# TSOC_NEOLED.net
KiCad netlist of a schematic drawn in EAGLE
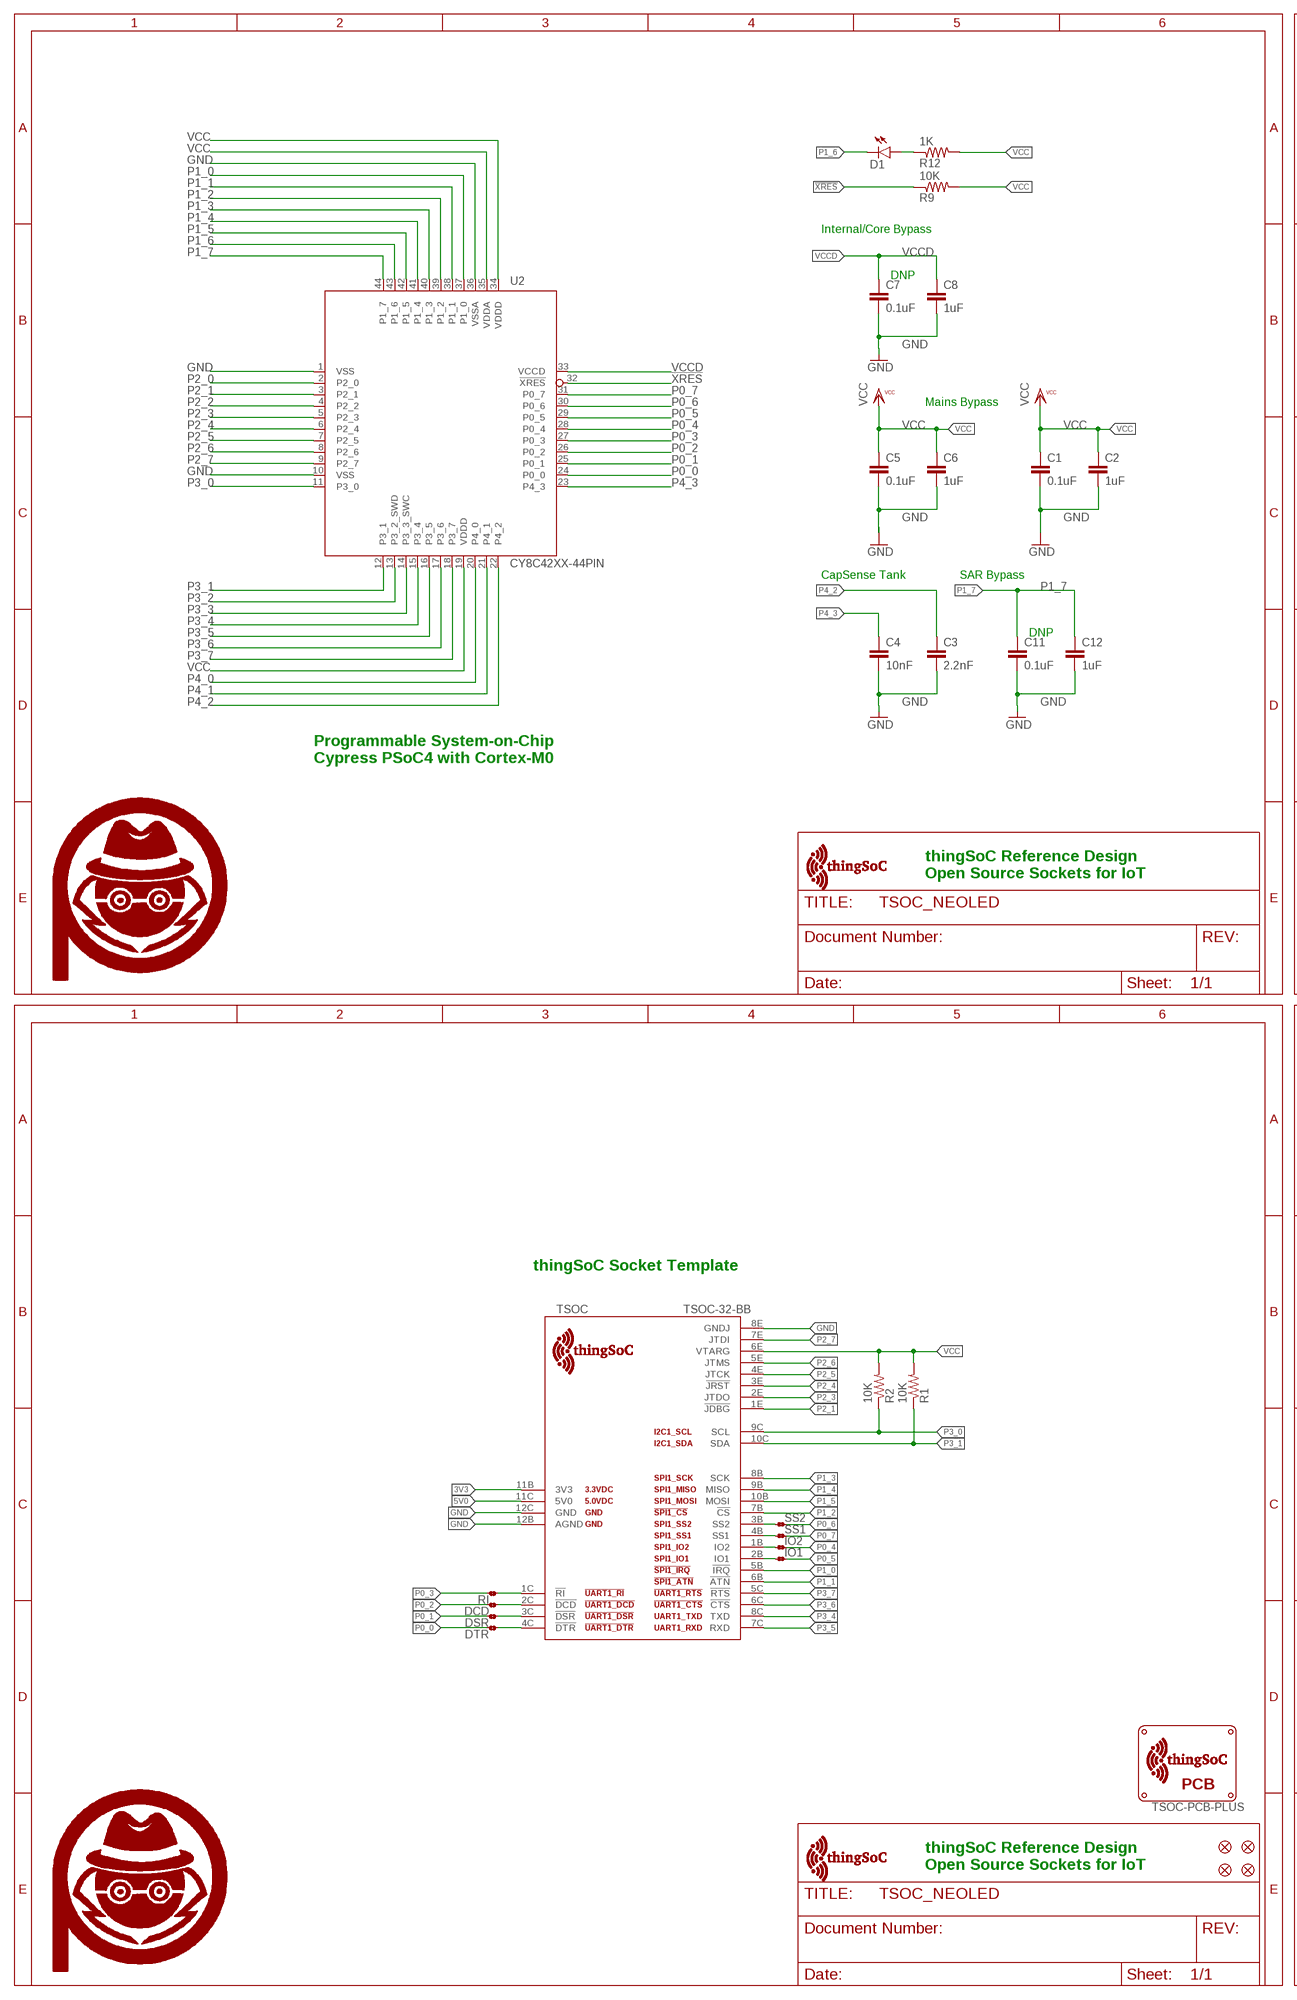
[diagram p0: schematic, sheet 1, part 1 of 2]
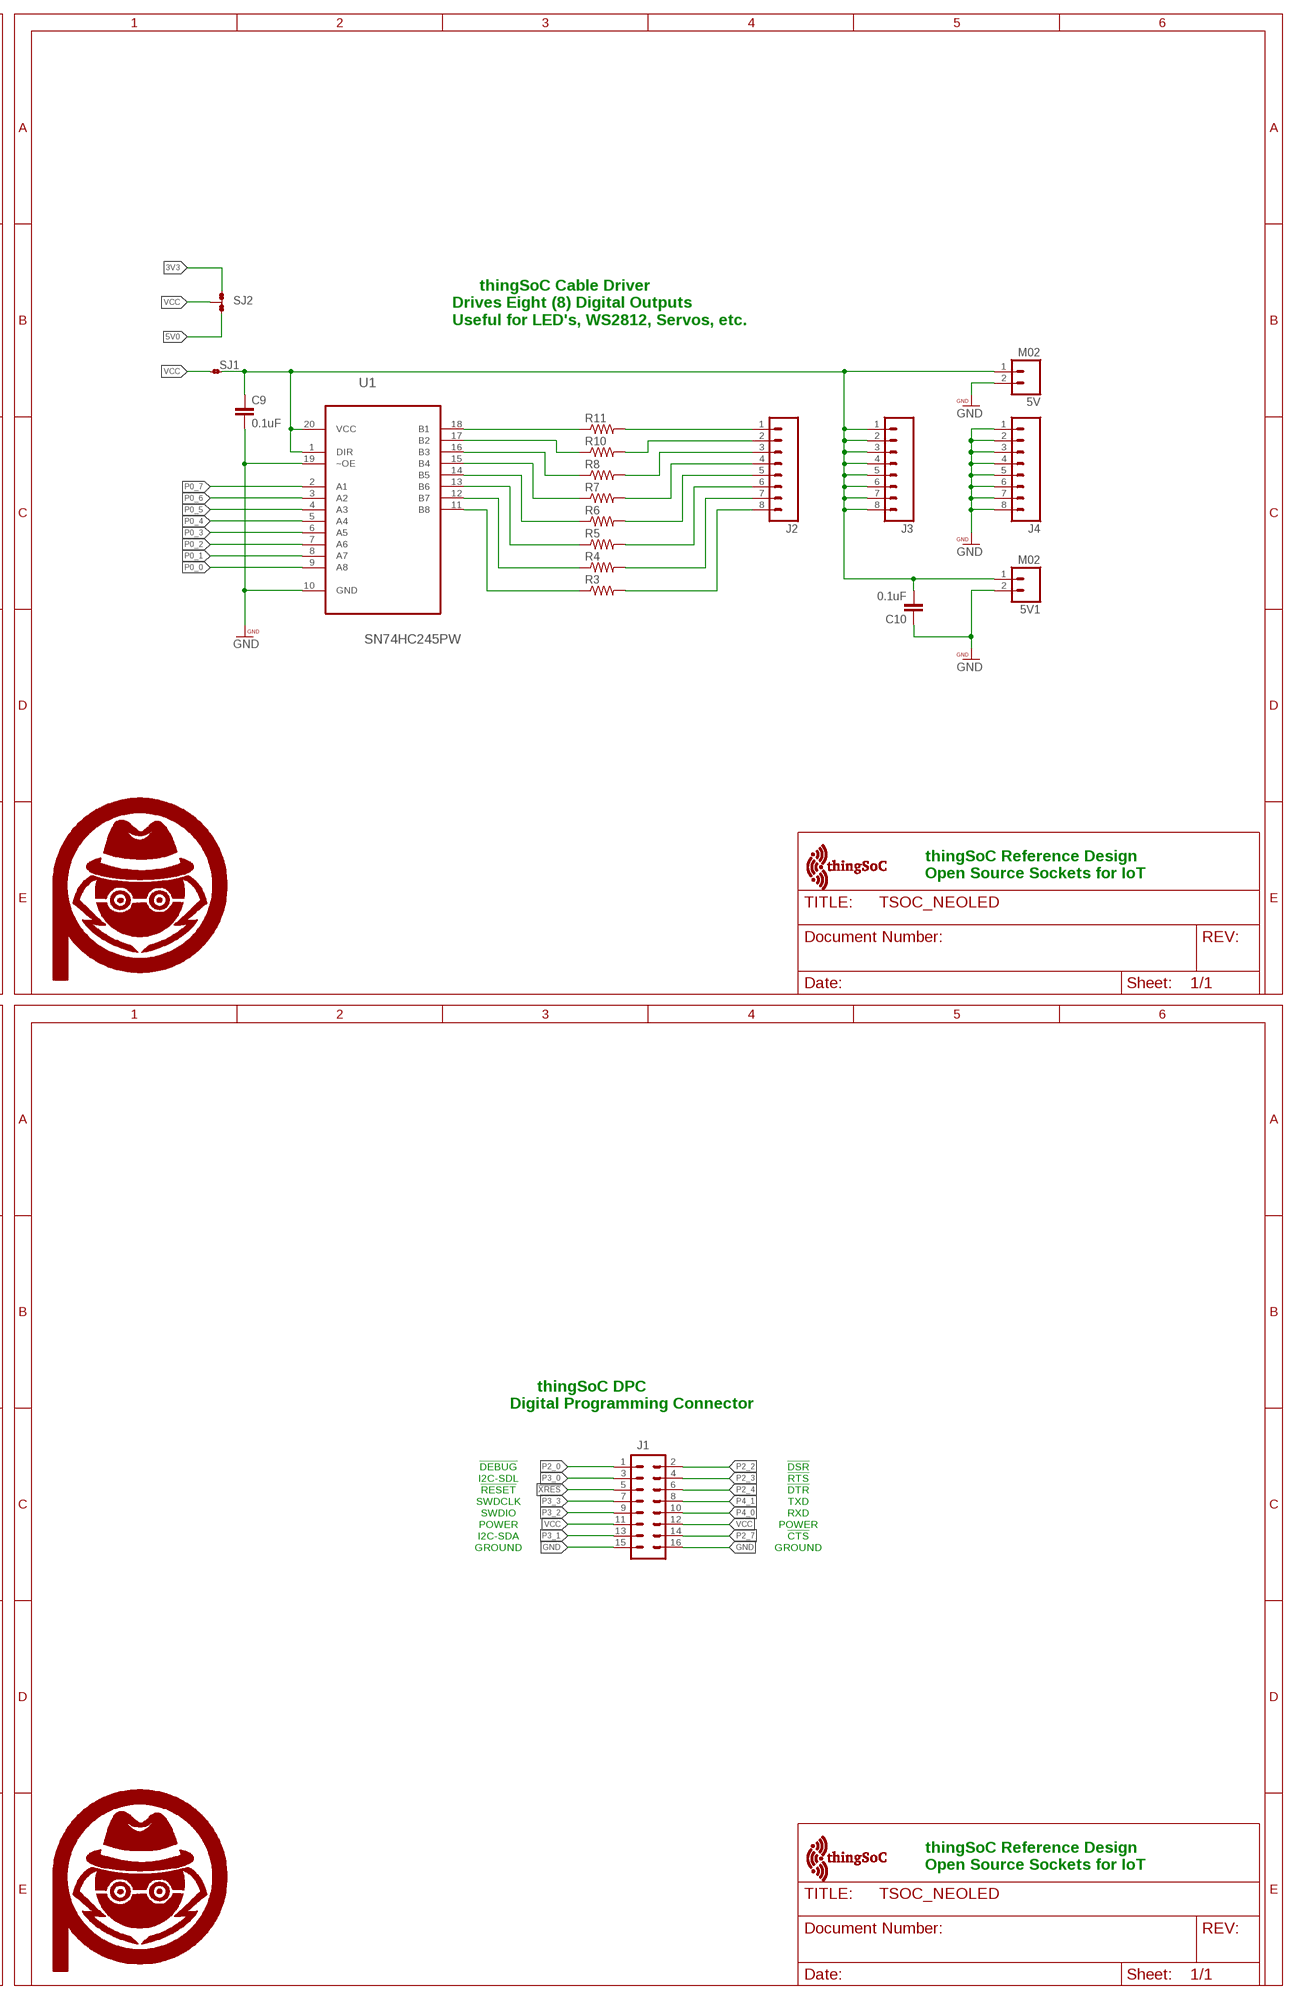
[diagram p1: schematic, sheet 1, part 2 of 2]

(export (version "E")
  (design (tool "Eeschema 10.0.6"))
  (components
    (comp (ref "$$U$1")
      (value "TSOC-LOGO-SMALL")
      (footprint "eagle-import:TSOC-LOGO-SML")
      (libsource (lib "eagle-import") (part "TSOC-LOGO-SMALL"))
    )
    (comp (ref "$$U$2")
      (value "TSOC-LOGO-MED")
      (footprint "eagle-import:TSOC-LOGO-MED")
      (libsource (lib "eagle-import") (part "TSOC-LOGO-MED"))
    )
    (comp (ref "5V")
      (value "M02")
      (footprint "eagle-import:1X02")
      (libsource (lib "eagle-import") (part "M02"))
    )
    (comp (ref "5V1")
      (value "M02")
      (footprint "eagle-import:1X02")
      (libsource (lib "eagle-import") (part "M02"))
    )
    (comp (ref "C1")
      (value "0.1uF")
      (footprint "eagle-import:0603-CAP")
      (libsource (lib "eagle-import") (part "CAP0603-CAP"))
    )
    (comp (ref "C2")
      (value "1uF")
      (footprint "eagle-import:0603-CAP")
      (libsource (lib "eagle-import") (part "CAP0603-CAP"))
    )
    (comp (ref "C3")
      (value "2.2nF")
      (footprint "eagle-import:0603-CAP")
      (libsource (lib "eagle-import") (part "CAP0603-CAP"))
    )
    (comp (ref "C4")
      (value "10nF")
      (footprint "eagle-import:0603-CAP")
      (libsource (lib "eagle-import") (part "CAP0603-CAP"))
    )
    (comp (ref "C5")
      (value "0.1uF")
      (footprint "eagle-import:0603-CAP")
      (libsource (lib "eagle-import") (part "CAP0603-CAP"))
    )
    (comp (ref "C6")
      (value "1uF")
      (footprint "eagle-import:0603-CAP")
      (libsource (lib "eagle-import") (part "CAP0603-CAP"))
    )
    (comp (ref "C7")
      (value "0.1uF")
      (footprint "eagle-import:0603-CAP")
      (libsource (lib "eagle-import") (part "CAP0603-CAP"))
    )
    (comp (ref "C8")
      (value "1uF")
      (footprint "eagle-import:0603-CAP")
      (libsource (lib "eagle-import") (part "CAP0603-CAP"))
    )
    (comp (ref "C9")
      (value "0.1uF")
      (footprint "eagle-import:0603-CAP")
      (libsource (lib "eagle-import") (part "CAP0603-CAP"))
    )
    (comp (ref "C10")
      (value "0.1uF")
      (footprint "eagle-import:0603-CAP")
      (libsource (lib "eagle-import") (part "CAP0603-CAP"))
    )
    (comp (ref "C11")
      (value "0.1uF")
      (footprint "eagle-import:0603-CAP")
      (libsource (lib "eagle-import") (part "CAP0603-CAP"))
    )
    (comp (ref "C12")
      (value "1uF")
      (footprint "eagle-import:0603-CAP")
      (libsource (lib "eagle-import") (part "CAP0603-CAP"))
    )
    (comp (ref "D1")
      (value "LED0603")
      (footprint "eagle-import:LED-0603")
      (libsource (lib "eagle-import") (part "LED0603"))
    )
    (comp (ref "DCD")
      (value "JMP-2-NO")
      (footprint "eagle-import:JMP-2-NO")
      (libsource (lib "eagle-import") (part "JMP-2-NO"))
    )
    (comp (ref "DSR")
      (value "JMP-2-NO")
      (footprint "eagle-import:JMP-2-NO")
      (libsource (lib "eagle-import") (part "JMP-2-NO"))
    )
    (comp (ref "DTR")
      (value "JMP-2-NO")
      (footprint "eagle-import:JMP-2-NO")
      (libsource (lib "eagle-import") (part "JMP-2-NO"))
    )
    (comp (ref "FID1")
      (value "FIDUCIALUFIDUCIAL")
      (footprint "eagle-import:MICRO-FIDUCIAL")
      (libsource (lib "eagle-import") (part "FIDUCIALUFIDUCIAL"))
    )
    (comp (ref "FID2")
      (value "FIDUCIALUFIDUCIAL")
      (footprint "eagle-import:MICRO-FIDUCIAL")
      (libsource (lib "eagle-import") (part "FIDUCIALUFIDUCIAL"))
    )
    (comp (ref "FID3")
      (value "FIDUCIALUFIDUCIAL")
      (footprint "eagle-import:MICRO-FIDUCIAL")
      (libsource (lib "eagle-import") (part "FIDUCIALUFIDUCIAL"))
    )
    (comp (ref "FID4")
      (value "FIDUCIALUFIDUCIAL")
      (footprint "eagle-import:MICRO-FIDUCIAL")
      (libsource (lib "eagle-import") (part "FIDUCIALUFIDUCIAL"))
    )
    (comp (ref "IO1")
      (value "JMP-2-NO")
      (footprint "eagle-import:JMP-2-NO")
      (libsource (lib "eagle-import") (part "JMP-2-NO"))
    )
    (comp (ref "IO2")
      (value "JMP-2-NO")
      (footprint "eagle-import:JMP-2-NO")
      (libsource (lib "eagle-import") (part "JMP-2-NO"))
    )
    (comp (ref "J1")
      (value "M08X2")
      (footprint "eagle-import:2X8")
      (libsource (lib "eagle-import") (part "M08X2"))
    )
    (comp (ref "J2")
      (value "M08")
      (footprint "eagle-import:1X08_ROUND")
      (libsource (lib "eagle-import") (part "M08"))
    )
    (comp (ref "J3")
      (value "M08")
      (footprint "eagle-import:1X08_ROUND")
      (libsource (lib "eagle-import") (part "M08"))
    )
    (comp (ref "J4")
      (value "M08")
      (footprint "eagle-import:1X08_ROUND")
      (libsource (lib "eagle-import") (part "M08"))
    )
    (comp (ref "R1")
      (value "10K")
      (footprint "eagle-import:0603-RES")
      (libsource (lib "eagle-import") (part "RESISTOR_SFE0603-RES"))
    )
    (comp (ref "R2")
      (value "10K")
      (footprint "eagle-import:0603-RES")
      (libsource (lib "eagle-import") (part "RESISTOR_SFE0603-RES"))
    )
    (comp (ref "R3")
      (value "RESISTOR0603-RES")
      (footprint "eagle-import:0603-RES")
      (libsource (lib "eagle-import") (part "RESISTOR0603-RES"))
    )
    (comp (ref "R4")
      (value "RESISTOR0603-RES")
      (footprint "eagle-import:0603-RES")
      (libsource (lib "eagle-import") (part "RESISTOR0603-RES"))
    )
    (comp (ref "R5")
      (value "RESISTOR0603-RES")
      (footprint "eagle-import:0603-RES")
      (libsource (lib "eagle-import") (part "RESISTOR0603-RES"))
    )
    (comp (ref "R6")
      (value "RESISTOR0603-RES")
      (footprint "eagle-import:0603-RES")
      (libsource (lib "eagle-import") (part "RESISTOR0603-RES"))
    )
    (comp (ref "R7")
      (value "RESISTOR0603-RES")
      (footprint "eagle-import:0603-RES")
      (libsource (lib "eagle-import") (part "RESISTOR0603-RES"))
    )
    (comp (ref "R8")
      (value "RESISTOR0603-RES")
      (footprint "eagle-import:0603-RES")
      (libsource (lib "eagle-import") (part "RESISTOR0603-RES"))
    )
    (comp (ref "R9")
      (value "10K")
      (footprint "eagle-import:0603-RES")
      (libsource (lib "eagle-import") (part "RESISTOR_SFE0603-RES"))
    )
    (comp (ref "R10")
      (value "RESISTOR0603-RES")
      (footprint "eagle-import:0603-RES")
      (libsource (lib "eagle-import") (part "RESISTOR0603-RES"))
    )
    (comp (ref "R11")
      (value "RESISTOR0603-RES")
      (footprint "eagle-import:0603-RES")
      (libsource (lib "eagle-import") (part "RESISTOR0603-RES"))
    )
    (comp (ref "R12")
      (value "1K")
      (footprint "eagle-import:0603-RES")
      (libsource (lib "eagle-import") (part "RESISTOR_SFE0603-RES"))
    )
    (comp (ref "RI")
      (value "JMP-2-NO")
      (footprint "eagle-import:JMP-2-NO")
      (libsource (lib "eagle-import") (part "JMP-2-NO"))
    )
    (comp (ref "SJ1")
      (value "JMP-2-NC")
      (footprint "eagle-import:JMP-2-NC")
      (libsource (lib "eagle-import") (part "JMP-2-NC"))
    )
    (comp (ref "SJ2")
      (value "JMP-3-NC")
      (footprint "eagle-import:JMP-3-NC")
      (libsource (lib "eagle-import") (part "JMP-3-NC"))
    )
    (comp (ref "SS1")
      (value "JMP-2-NO")
      (footprint "eagle-import:JMP-2-NO")
      (libsource (lib "eagle-import") (part "JMP-2-NO"))
    )
    (comp (ref "SS2")
      (value "JMP-2-NO")
      (footprint "eagle-import:JMP-2-NO")
      (libsource (lib "eagle-import") (part "JMP-2-NO"))
    )
    (comp (ref "TSOC")
      (value "TSOC-32-BB")
      (footprint "eagle-import:TSOC-BB-S32")
      (libsource (lib "eagle-import") (part "TSOC-32-BB"))
    )
    (comp (ref "U$1")
      (value "TSOC-PCB-PLUS")
      (footprint "eagle-import:TSOC-BB-BRD-PLUS")
      (libsource (lib "eagle-import") (part "TSOC-PCB-PLUS"))
    )
    (comp (ref "U$3")
      (value "PA_LOGO_SYMNULL")
      (footprint "eagle-import:NULL_SYM")
      (libsource (lib "eagle-import") (part "PA_LOGO_SYMNULL"))
    )
    (comp (ref "U$9")
      (value "PA_LOGO_SYMNULL")
      (footprint "eagle-import:NULL_SYM")
      (libsource (lib "eagle-import") (part "PA_LOGO_SYMNULL"))
    )
    (comp (ref "U$10")
      (value "PA_LOGO_SYMNULL")
      (footprint "eagle-import:NULL_SYM")
      (libsource (lib "eagle-import") (part "PA_LOGO_SYMNULL"))
    )
    (comp (ref "U$11")
      (value "PA_LOGO_SYMNULL")
      (footprint "eagle-import:NULL_SYM")
      (libsource (lib "eagle-import") (part "PA_LOGO_SYMNULL"))
    )
    (comp (ref "U$100")
      (value "TSOC-LOGO-SMALL")
      (footprint "eagle-import:TSOC-LOGO-SML")
      (libsource (lib "eagle-import") (part "TSOC-LOGO-SMALL"))
    )
    (comp (ref "U$101")
      (value "TSOC-LOGO-LRG")
      (footprint "eagle-import:TSOC-LOGO-LRG")
      (libsource (lib "eagle-import") (part "TSOC-LOGO-LRG"))
    )
    (comp (ref "U1")
      (value "SN74HC245PW")
      (footprint "eagle-import:SOP65P640X120-20N")
      (libsource (lib "eagle-import") (part "SN74HC245PW"))
    )
    (comp (ref "U2")
      (value "CY8C42XX-44PIN")
      (footprint "eagle-import:TQFP-10X10-44")
      (libsource (lib "eagle-import") (part "CY8C42XX-44PIN"))
    )
  )
  (nets
    (net (code "1") (name "/~{XRES}") (class "Default")
      (node (ref "J1") (pin "5") (pinfunction "5_5") (pintype "passive"))
      (node (ref "R9") (pin "1") (pinfunction "1_1") (pintype "passive"))
      (node (ref "U2") (pin "32") (pinfunction "~{XRES}_32") (pintype "bidirectional"))
    )
    (net (code "2") (name "3V3") (class "Default")
      (node (ref "SJ2") (pin "1") (pinfunction "1_1") (pintype "passive"))
      (node (ref "TSOC") (pin "11B") (pinfunction "3V3_11B") (pintype "bidirectional"))
    )
    (net (code "3") (name "5V0") (class "Default")
      (node (ref "SJ2") (pin "3") (pinfunction "3_3") (pintype "passive"))
      (node (ref "TSOC") (pin "11C") (pinfunction "5V0_11C") (pintype "bidirectional"))
    )
    (net (code "4") (name "GND") (class "Default")
      (node (ref "5V") (pin "2") (pinfunction "2_2") (pintype "passive"))
      (node (ref "5V1") (pin "2") (pinfunction "2_2") (pintype "passive"))
      (node (ref "C1") (pin "2") (pinfunction "2_2") (pintype "passive"))
      (node (ref "C10") (pin "1") (pinfunction "1_1") (pintype "passive"))
      (node (ref "C11") (pin "2") (pinfunction "2_2") (pintype "passive"))
      (node (ref "C12") (pin "2") (pinfunction "2_2") (pintype "passive"))
      (node (ref "C2") (pin "2") (pinfunction "2_2") (pintype "passive"))
      (node (ref "C3") (pin "2") (pinfunction "2_2") (pintype "passive"))
      (node (ref "C4") (pin "2") (pinfunction "2_2") (pintype "passive"))
      (node (ref "C5") (pin "2") (pinfunction "2_2") (pintype "passive"))
      (node (ref "C6") (pin "2") (pinfunction "2_2") (pintype "passive"))
      (node (ref "C7") (pin "2") (pinfunction "2_2") (pintype "passive"))
      (node (ref "C8") (pin "2") (pinfunction "2_2") (pintype "passive"))
      (node (ref "C9") (pin "2") (pinfunction "2_2") (pintype "passive"))
      (node (ref "J1") (pin "15") (pinfunction "15_15") (pintype "passive"))
      (node (ref "J1") (pin "16") (pinfunction "16_16") (pintype "passive"))
      (node (ref "J4") (pin "1") (pinfunction "1_1") (pintype "passive"))
      (node (ref "J4") (pin "2") (pinfunction "2_2") (pintype "passive"))
      (node (ref "J4") (pin "3") (pinfunction "3_3") (pintype "passive"))
      (node (ref "J4") (pin "4") (pinfunction "4_4") (pintype "passive"))
      (node (ref "J4") (pin "5") (pinfunction "5_5") (pintype "passive"))
      (node (ref "J4") (pin "6") (pinfunction "6_6") (pintype "passive"))
      (node (ref "J4") (pin "7") (pinfunction "7_7") (pintype "passive"))
      (node (ref "J4") (pin "8") (pinfunction "8_8") (pintype "passive"))
      (node (ref "TSOC") (pin "12B") (pinfunction "AGND_12B") (pintype "bidirectional"))
      (node (ref "TSOC") (pin "12C") (pinfunction "GND_12C") (pintype "bidirectional"))
      (node (ref "TSOC") (pin "8E") (pinfunction "GNDJ_8E") (pintype "bidirectional"))
      (node (ref "U1") (pin "10") (pinfunction "GND_10") (pintype "input"))
      (node (ref "U1") (pin "19") (pinfunction "~{OE}_19") (pintype "input"))
      (node (ref "U2") (pin "1") (pinfunction "VSS_1") (pintype "bidirectional"))
      (node (ref "U2") (pin "10") (pinfunction "VSS_10") (pintype "bidirectional"))
      (node (ref "U2") (pin "36") (pinfunction "VSSA_36") (pintype "bidirectional"))
    )
    (net (code "5") (name "Net-(D1-PadA)") (class "Default")
      (node (ref "D1") (pin "A") (pinfunction "A_A") (pintype "passive"))
      (node (ref "R12") (pin "1") (pinfunction "1_1") (pintype "passive"))
    )
    (net (code "6") (name "Net-(J2-Pad1)") (class "Default")
      (node (ref "J2") (pin "1") (pinfunction "1_1") (pintype "passive"))
      (node (ref "R11") (pin "2") (pinfunction "2_2") (pintype "passive"))
    )
    (net (code "7") (name "Net-(J2-Pad2)") (class "Default")
      (node (ref "J2") (pin "2") (pinfunction "2_2") (pintype "passive"))
      (node (ref "R10") (pin "2") (pinfunction "2_2") (pintype "passive"))
    )
    (net (code "8") (name "Net-(J2-Pad3)") (class "Default")
      (node (ref "J2") (pin "3") (pinfunction "3_3") (pintype "passive"))
      (node (ref "R8") (pin "2") (pinfunction "2_2") (pintype "passive"))
    )
    (net (code "9") (name "Net-(J2-Pad4)") (class "Default")
      (node (ref "J2") (pin "4") (pinfunction "4_4") (pintype "passive"))
      (node (ref "R7") (pin "2") (pinfunction "2_2") (pintype "passive"))
    )
    (net (code "10") (name "Net-(J2-Pad5)") (class "Default")
      (node (ref "J2") (pin "5") (pinfunction "5_5") (pintype "passive"))
      (node (ref "R6") (pin "2") (pinfunction "2_2") (pintype "passive"))
    )
    (net (code "11") (name "Net-(J2-Pad6)") (class "Default")
      (node (ref "J2") (pin "6") (pinfunction "6_6") (pintype "passive"))
      (node (ref "R5") (pin "2") (pinfunction "2_2") (pintype "passive"))
    )
    (net (code "12") (name "Net-(J2-Pad7)") (class "Default")
      (node (ref "J2") (pin "7") (pinfunction "7_7") (pintype "passive"))
      (node (ref "R4") (pin "2") (pinfunction "2_2") (pintype "passive"))
    )
    (net (code "13") (name "Net-(J2-Pad8)") (class "Default")
      (node (ref "J2") (pin "8") (pinfunction "8_8") (pintype "passive"))
      (node (ref "R3") (pin "2") (pinfunction "2_2") (pintype "passive"))
    )
    (net (code "14") (name "Net-(TSOC-IO1)") (class "Default")
      (node (ref "IO1") (pin "1") (pinfunction "1_1") (pintype "passive"))
      (node (ref "TSOC") (pin "2B") (pinfunction "IO1_2B") (pintype "bidirectional"))
    )
    (net (code "15") (name "Net-(TSOC-IO2)") (class "Default")
      (node (ref "IO2") (pin "1") (pinfunction "1_1") (pintype "passive"))
      (node (ref "TSOC") (pin "1B") (pinfunction "IO2_1B") (pintype "bidirectional"))
    )
    (net (code "16") (name "Net-(TSOC-SS1)") (class "Default")
      (node (ref "SS1") (pin "1") (pinfunction "1_1") (pintype "passive"))
      (node (ref "TSOC") (pin "4B") (pinfunction "SS1_4B") (pintype "bidirectional"))
    )
    (net (code "17") (name "Net-(TSOC-SS2)") (class "Default")
      (node (ref "SS2") (pin "1") (pinfunction "1_1") (pintype "passive"))
      (node (ref "TSOC") (pin "3B") (pinfunction "SS2_3B") (pintype "bidirectional"))
    )
    (net (code "18") (name "Net-(TSOC-~{DCD})") (class "Default")
      (node (ref "DCD") (pin "1") (pinfunction "1_1") (pintype "passive"))
      (node (ref "TSOC") (pin "2C") (pinfunction "~{DCD}_2C") (pintype "bidirectional"))
    )
    (net (code "19") (name "Net-(TSOC-~{DSR})") (class "Default")
      (node (ref "DSR") (pin "1") (pinfunction "1_1") (pintype "passive"))
      (node (ref "TSOC") (pin "3C") (pinfunction "~{DSR}_3C") (pintype "bidirectional"))
    )
    (net (code "20") (name "Net-(TSOC-~{DTR})") (class "Default")
      (node (ref "DTR") (pin "1") (pinfunction "1_1") (pintype "passive"))
      (node (ref "TSOC") (pin "4C") (pinfunction "~{DTR}_4C") (pintype "bidirectional"))
    )
    (net (code "21") (name "Net-(TSOC-~{RI})") (class "Default")
      (node (ref "RI") (pin "1") (pinfunction "1_1") (pintype "passive"))
      (node (ref "TSOC") (pin "1C") (pinfunction "~{RI}_1C") (pintype "bidirectional"))
    )
    (net (code "22") (name "Net-(U1-B1)") (class "Default")
      (node (ref "R11") (pin "1") (pinfunction "1_1") (pintype "passive"))
      (node (ref "U1") (pin "18") (pinfunction "B1_18") (pintype "bidirectional"))
    )
    (net (code "23") (name "Net-(U1-B2)") (class "Default")
      (node (ref "R10") (pin "1") (pinfunction "1_1") (pintype "passive"))
      (node (ref "U1") (pin "17") (pinfunction "B2_17") (pintype "bidirectional"))
    )
    (net (code "24") (name "Net-(U1-B3)") (class "Default")
      (node (ref "R8") (pin "1") (pinfunction "1_1") (pintype "passive"))
      (node (ref "U1") (pin "16") (pinfunction "B3_16") (pintype "bidirectional"))
    )
    (net (code "25") (name "Net-(U1-B4)") (class "Default")
      (node (ref "R7") (pin "1") (pinfunction "1_1") (pintype "passive"))
      (node (ref "U1") (pin "15") (pinfunction "B4_15") (pintype "bidirectional"))
    )
    (net (code "26") (name "Net-(U1-B5)") (class "Default")
      (node (ref "R6") (pin "1") (pinfunction "1_1") (pintype "passive"))
      (node (ref "U1") (pin "14") (pinfunction "B5_14") (pintype "bidirectional"))
    )
    (net (code "27") (name "Net-(U1-B6)") (class "Default")
      (node (ref "R5") (pin "1") (pinfunction "1_1") (pintype "passive"))
      (node (ref "U1") (pin "13") (pinfunction "B6_13") (pintype "bidirectional"))
    )
    (net (code "28") (name "Net-(U1-B7)") (class "Default")
      (node (ref "R4") (pin "1") (pinfunction "1_1") (pintype "passive"))
      (node (ref "U1") (pin "12") (pinfunction "B7_12") (pintype "bidirectional"))
    )
    (net (code "29") (name "Net-(U1-B8)") (class "Default")
      (node (ref "R3") (pin "1") (pinfunction "1_1") (pintype "passive"))
      (node (ref "U1") (pin "11") (pinfunction "B8_11") (pintype "bidirectional"))
    )
    (net (code "30") (name "Net-(U1-DIR)") (class "Default")
      (node (ref "5V") (pin "1") (pinfunction "1_1") (pintype "passive"))
      (node (ref "5V1") (pin "1") (pinfunction "1_1") (pintype "passive"))
      (node (ref "C10") (pin "2") (pinfunction "2_2") (pintype "passive"))
      (node (ref "C9") (pin "1") (pinfunction "1_1") (pintype "passive"))
      (node (ref "J3") (pin "1") (pinfunction "1_1") (pintype "passive"))
      (node (ref "J3") (pin "2") (pinfunction "2_2") (pintype "passive"))
      (node (ref "J3") (pin "3") (pinfunction "3_3") (pintype "passive"))
      (node (ref "J3") (pin "4") (pinfunction "4_4") (pintype "passive"))
      (node (ref "J3") (pin "5") (pinfunction "5_5") (pintype "passive"))
      (node (ref "J3") (pin "6") (pinfunction "6_6") (pintype "passive"))
      (node (ref "J3") (pin "7") (pinfunction "7_7") (pintype "passive"))
      (node (ref "J3") (pin "8") (pinfunction "8_8") (pintype "passive"))
      (node (ref "SJ1") (pin "2") (pinfunction "2_2") (pintype "passive"))
      (node (ref "U1") (pin "1") (pinfunction "DIR_1") (pintype "input"))
      (node (ref "U1") (pin "20") (pinfunction "VCC_20") (pintype "power_in"))
    )
    (net (code "31") (name "P0_0") (class "Default")
      (node (ref "DTR") (pin "2") (pinfunction "2_2") (pintype "passive"))
      (node (ref "U1") (pin "9") (pinfunction "A8_9") (pintype "bidirectional"))
      (node (ref "U2") (pin "24") (pinfunction "P0_0_24") (pintype "bidirectional"))
    )
    (net (code "32") (name "P0_1") (class "Default")
      (node (ref "DSR") (pin "2") (pinfunction "2_2") (pintype "passive"))
      (node (ref "U1") (pin "8") (pinfunction "A7_8") (pintype "bidirectional"))
      (node (ref "U2") (pin "25") (pinfunction "P0_1_25") (pintype "bidirectional"))
    )
    (net (code "33") (name "P0_2") (class "Default")
      (node (ref "DCD") (pin "2") (pinfunction "2_2") (pintype "passive"))
      (node (ref "U1") (pin "7") (pinfunction "A6_7") (pintype "bidirectional"))
      (node (ref "U2") (pin "26") (pinfunction "P0_2_26") (pintype "input"))
    )
    (net (code "34") (name "P0_3") (class "Default")
      (node (ref "RI") (pin "2") (pinfunction "2_2") (pintype "passive"))
      (node (ref "U1") (pin "6") (pinfunction "A5_6") (pintype "bidirectional"))
      (node (ref "U2") (pin "27") (pinfunction "P0_3_27") (pintype "bidirectional"))
    )
    (net (code "35") (name "P0_4") (class "Default")
      (node (ref "IO2") (pin "2") (pinfunction "2_2") (pintype "passive"))
      (node (ref "U1") (pin "5") (pinfunction "A4_5") (pintype "bidirectional"))
      (node (ref "U2") (pin "28") (pinfunction "P0_4_28") (pintype "bidirectional"))
    )
    (net (code "36") (name "P0_5") (class "Default")
      (node (ref "IO1") (pin "2") (pinfunction "2_2") (pintype "passive"))
      (node (ref "U1") (pin "4") (pinfunction "A3_4") (pintype "bidirectional"))
      (node (ref "U2") (pin "29") (pinfunction "P0_5_29") (pintype "bidirectional"))
    )
    (net (code "37") (name "P0_6") (class "Default")
      (node (ref "SS2") (pin "2") (pinfunction "2_2") (pintype "passive"))
      (node (ref "U1") (pin "3") (pinfunction "A2_3") (pintype "bidirectional"))
      (node (ref "U2") (pin "30") (pinfunction "P0_6_30") (pintype "power_in"))
    )
    (net (code "38") (name "P0_7") (class "Default")
      (node (ref "SS1") (pin "2") (pinfunction "2_2") (pintype "passive"))
      (node (ref "U1") (pin "2") (pinfunction "A1_2") (pintype "bidirectional"))
      (node (ref "U2") (pin "31") (pinfunction "P0_7_31") (pintype "bidirectional"))
    )
    (net (code "39") (name "P1_0") (class "Default")
      (node (ref "TSOC") (pin "5B") (pinfunction "~{IRQ}_5B") (pintype "bidirectional"))
      (node (ref "U2") (pin "37") (pinfunction "P1_0_37") (pintype "bidirectional"))
    )
    (net (code "40") (name "P1_1") (class "Default")
      (node (ref "TSOC") (pin "6B") (pinfunction "~{ATN}_6B") (pintype "bidirectional"))
      (node (ref "U2") (pin "38") (pinfunction "P1_1_38") (pintype "bidirectional"))
    )
    (net (code "41") (name "P1_2") (class "Default")
      (node (ref "TSOC") (pin "7B") (pinfunction "~{CS}_7B") (pintype "bidirectional"))
      (node (ref "U2") (pin "39") (pinfunction "P1_2_39") (pintype "power_in"))
    )
    (net (code "42") (name "P1_3") (class "Default")
      (node (ref "TSOC") (pin "8B") (pinfunction "SCK_8B") (pintype "bidirectional"))
      (node (ref "U2") (pin "40") (pinfunction "P1_3_40") (pintype "bidirectional"))
    )
    (net (code "43") (name "P1_4") (class "Default")
      (node (ref "TSOC") (pin "9B") (pinfunction "MISO_9B") (pintype "bidirectional"))
      (node (ref "U2") (pin "41") (pinfunction "P1_4_41") (pintype "bidirectional"))
    )
    (net (code "44") (name "P1_5") (class "Default")
      (node (ref "TSOC") (pin "10B") (pinfunction "MOSI_10B") (pintype "bidirectional"))
      (node (ref "U2") (pin "42") (pinfunction "P1_5_42") (pintype "bidirectional"))
    )
    (net (code "45") (name "P1_6") (class "Default")
      (node (ref "D1") (pin "C") (pinfunction "C_C") (pintype "passive"))
      (node (ref "U2") (pin "43") (pinfunction "P1_6_43") (pintype "bidirectional"))
    )
    (net (code "46") (name "P1_7") (class "Default")
      (node (ref "C11") (pin "1") (pinfunction "1_1") (pintype "passive"))
      (node (ref "C12") (pin "1") (pinfunction "1_1") (pintype "passive"))
      (node (ref "U2") (pin "44") (pinfunction "P1_7_44") (pintype "bidirectional"))
    )
    (net (code "47") (name "P2_0") (class "Default")
      (node (ref "J1") (pin "1") (pinfunction "1_1") (pintype "passive"))
      (node (ref "U2") (pin "2") (pinfunction "P2_0_2") (pintype "bidirectional"))
    )
    (net (code "48") (name "P2_1") (class "Default")
      (node (ref "TSOC") (pin "1E") (pinfunction "~{JDBG}_1E") (pintype "bidirectional"))
      (node (ref "U2") (pin "3") (pinfunction "P2_1_3") (pintype "bidirectional"))
    )
    (net (code "49") (name "P2_2") (class "Default")
      (node (ref "J1") (pin "2") (pinfunction "2_2") (pintype "passive"))
      (node (ref "U2") (pin "4") (pinfunction "P2_2_4") (pintype "power_in"))
    )
    (net (code "50") (name "P2_3") (class "Default")
      (node (ref "J1") (pin "4") (pinfunction "4_4") (pintype "passive"))
      (node (ref "TSOC") (pin "2E") (pinfunction "JTDO_2E") (pintype "bidirectional"))
      (node (ref "U2") (pin "5") (pinfunction "P2_3_5") (pintype "bidirectional"))
    )
    (net (code "51") (name "P2_4") (class "Default")
      (node (ref "J1") (pin "6") (pinfunction "6_6") (pintype "passive"))
      (node (ref "TSOC") (pin "3E") (pinfunction "~{JRST}_3E") (pintype "bidirectional"))
      (node (ref "U2") (pin "6") (pinfunction "P2_4_6") (pintype "bidirectional"))
    )
    (net (code "52") (name "P2_5") (class "Default")
      (node (ref "TSOC") (pin "4E") (pinfunction "JTCK_4E") (pintype "bidirectional"))
      (node (ref "U2") (pin "7") (pinfunction "P2_5_7") (pintype "bidirectional"))
    )
    (net (code "53") (name "P2_6") (class "Default")
      (node (ref "TSOC") (pin "5E") (pinfunction "JTMS_5E") (pintype "bidirectional"))
      (node (ref "U2") (pin "8") (pinfunction "P2_6_8") (pintype "power_in"))
    )
    (net (code "54") (name "P2_7") (class "Default")
      (node (ref "J1") (pin "14") (pinfunction "14_14") (pintype "passive"))
      (node (ref "TSOC") (pin "7E") (pinfunction "JTDI_7E") (pintype "bidirectional"))
      (node (ref "U2") (pin "9") (pinfunction "P2_7_9") (pintype "bidirectional"))
    )
    (net (code "55") (name "P3_0") (class "Default")
      (node (ref "J1") (pin "3") (pinfunction "3_3") (pintype "passive"))
      (node (ref "R2") (pin "1") (pinfunction "1_1") (pintype "passive"))
      (node (ref "TSOC") (pin "9C") (pinfunction "SCL_9C") (pintype "bidirectional"))
      (node (ref "U2") (pin "11") (pinfunction "P3_0_11") (pintype "bidirectional"))
    )
    (net (code "56") (name "P3_1") (class "Default")
      (node (ref "J1") (pin "13") (pinfunction "13_13") (pintype "passive"))
      (node (ref "R1") (pin "1") (pinfunction "1_1") (pintype "passive"))
      (node (ref "TSOC") (pin "10C") (pinfunction "SDA_10C") (pintype "bidirectional"))
      (node (ref "U2") (pin "12") (pinfunction "P3_1_12") (pintype "bidirectional"))
    )
    (net (code "57") (name "P3_2") (class "Default")
      (node (ref "J1") (pin "9") (pinfunction "9_9") (pintype "passive"))
      (node (ref "U2") (pin "13") (pinfunction "P3_2_SWD_13") (pintype "bidirectional"))
    )
    (net (code "58") (name "P3_3") (class "Default")
      (node (ref "J1") (pin "7") (pinfunction "7_7") (pintype "passive"))
      (node (ref "U2") (pin "14") (pinfunction "P3_3_SWC_14") (pintype "bidirectional"))
    )
    (net (code "59") (name "P3_4") (class "Default")
      (node (ref "TSOC") (pin "8C") (pinfunction "TXD_8C") (pintype "bidirectional"))
      (node (ref "U2") (pin "15") (pinfunction "P3_4_15") (pintype "bidirectional"))
    )
    (net (code "60") (name "P3_5") (class "Default")
      (node (ref "TSOC") (pin "7C") (pinfunction "RXD_7C") (pintype "bidirectional"))
      (node (ref "U2") (pin "16") (pinfunction "P3_5_16") (pintype "bidirectional"))
    )
    (net (code "61") (name "P3_6") (class "Default")
      (node (ref "TSOC") (pin "6C") (pinfunction "~{CTS}_6C") (pintype "bidirectional"))
      (node (ref "U2") (pin "17") (pinfunction "P3_6_17") (pintype "power_in"))
    )
    (net (code "62") (name "P3_7") (class "Default")
      (node (ref "TSOC") (pin "5C") (pinfunction "~{RTS}_5C") (pintype "bidirectional"))
      (node (ref "U2") (pin "18") (pinfunction "P3_7_18") (pintype "bidirectional"))
    )
    (net (code "63") (name "P4_0") (class "Default")
      (node (ref "J1") (pin "10") (pinfunction "10_10") (pintype "passive"))
      (node (ref "U2") (pin "20") (pinfunction "P4_0_20") (pintype "bidirectional"))
    )
    (net (code "64") (name "P4_1") (class "Default")
      (node (ref "J1") (pin "8") (pinfunction "8_8") (pintype "passive"))
      (node (ref "U2") (pin "21") (pinfunction "P4_1_21") (pintype "bidirectional"))
    )
    (net (code "65") (name "P4_2") (class "Default")
      (node (ref "C3") (pin "1") (pinfunction "1_1") (pintype "passive"))
      (node (ref "U2") (pin "22") (pinfunction "P4_2_22") (pintype "bidirectional"))
    )
    (net (code "66") (name "P4_3") (class "Default")
      (node (ref "C4") (pin "1") (pinfunction "1_1") (pintype "passive"))
      (node (ref "U2") (pin "23") (pinfunction "P4_3_23") (pintype "bidirectional"))
    )
    (net (code "67") (name "VCC") (class "Default")
      (node (ref "C1") (pin "1") (pinfunction "1_1") (pintype "passive"))
      (node (ref "C2") (pin "1") (pinfunction "1_1") (pintype "passive"))
      (node (ref "C5") (pin "1") (pinfunction "1_1") (pintype "passive"))
      (node (ref "C6") (pin "1") (pinfunction "1_1") (pintype "passive"))
      (node (ref "J1") (pin "11") (pinfunction "11_11") (pintype "passive"))
      (node (ref "J1") (pin "12") (pinfunction "12_12") (pintype "passive"))
      (node (ref "R1") (pin "2") (pinfunction "2_2") (pintype "passive"))
      (node (ref "R12") (pin "2") (pinfunction "2_2") (pintype "passive"))
      (node (ref "R2") (pin "2") (pinfunction "2_2") (pintype "passive"))
      (node (ref "R9") (pin "2") (pinfunction "2_2") (pintype "passive"))
      (node (ref "SJ1") (pin "1") (pinfunction "1_1") (pintype "passive"))
      (node (ref "SJ2") (pin "2") (pinfunction "2_2") (pintype "passive"))
      (node (ref "TSOC") (pin "6E") (pinfunction "VTARG_6E") (pintype "bidirectional"))
      (node (ref "U2") (pin "19") (pinfunction "VDDD_19") (pintype "bidirectional"))
      (node (ref "U2") (pin "34") (pinfunction "VDDD_34") (pintype "bidirectional"))
      (node (ref "U2") (pin "35") (pinfunction "VDDA_35") (pintype "bidirectional"))
    )
    (net (code "68") (name "VCCD") (class "Default")
      (node (ref "C7") (pin "1") (pinfunction "1_1") (pintype "passive"))
      (node (ref "C8") (pin "1") (pinfunction "1_1") (pintype "passive"))
      (node (ref "U2") (pin "33") (pinfunction "VCCD_33") (pintype "bidirectional"))
    )
  )
)
